# meArm.net
KiCad netlist of a schematic drawn in EAGLE
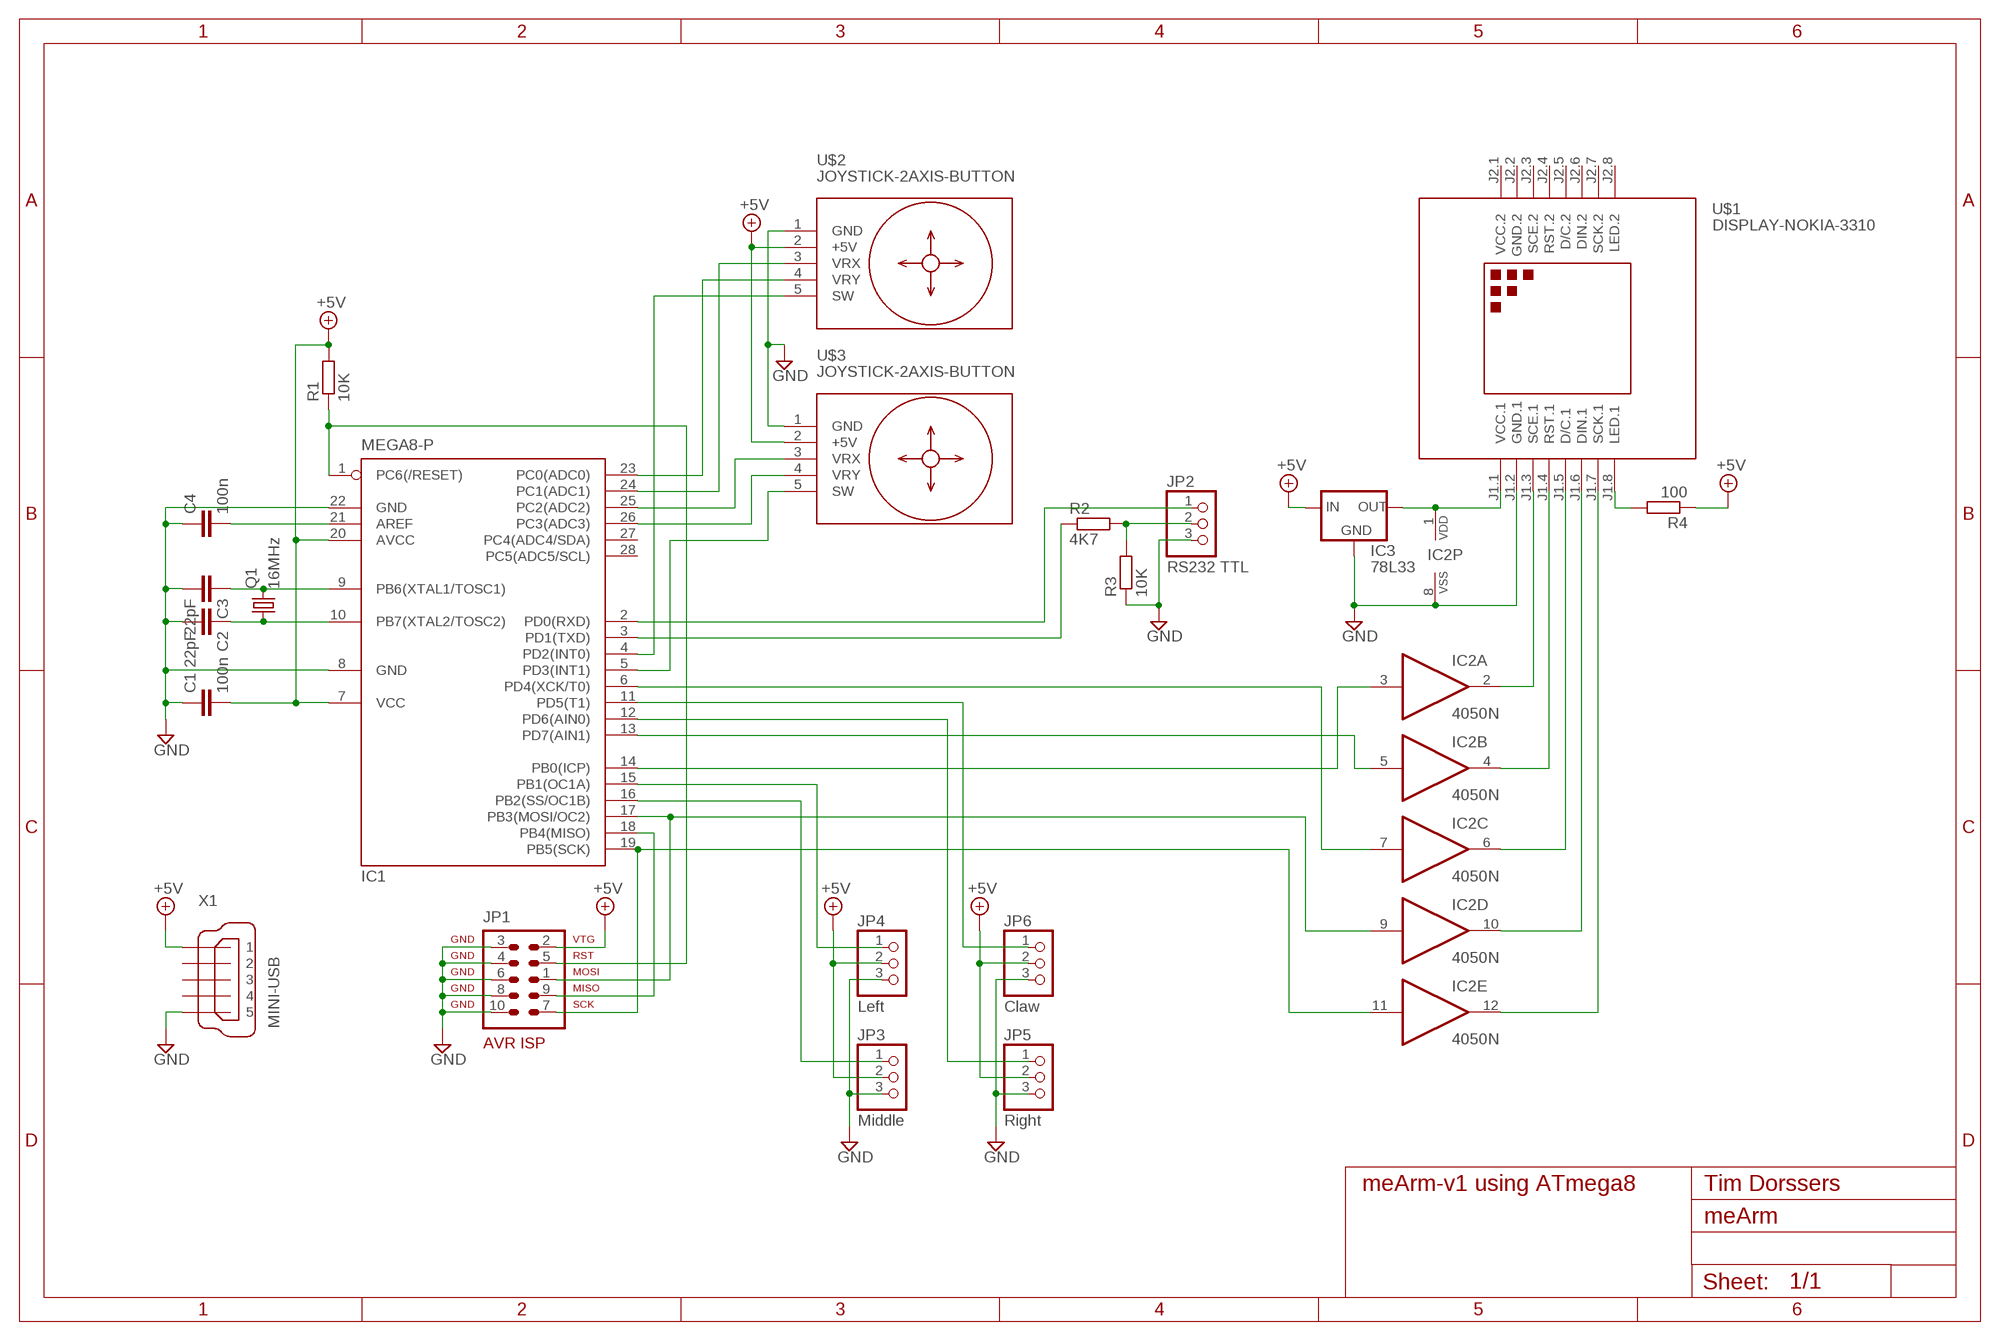
[diagram p0: schematic, sheet 1]

(export (version "E")
  (design (tool "Eeschema 10.0.6"))
  (components
    (comp (ref "C1")
      (value "100n")
      (footprint "eagle-import:C025-025X050")
      (libsource (lib "eagle-import") (part "C-EU025-025X050"))
    )
    (comp (ref "C2")
      (value "22pF")
      (footprint "eagle-import:C025-024X044")
      (libsource (lib "eagle-import") (part "C-EU025-024X044"))
    )
    (comp (ref "C3")
      (value "22pF")
      (footprint "eagle-import:C025-024X044")
      (libsource (lib "eagle-import") (part "C-EU025-024X044"))
    )
    (comp (ref "C4")
      (value "100n")
      (footprint "eagle-import:C025-025X050")
      (libsource (lib "eagle-import") (part "C-EU025-025X050"))
    )
    (comp (ref "IC1")
      (value "MEGA8-P")
      (footprint "eagle-import:DIL28-3")
      (libsource (lib "eagle-import") (part "MEGA8-P"))
    )
    (comp (ref "IC2")
      (value "4050N")
      (footprint "eagle-import:DIL16")
      (libsource (lib "eagle-import") (part "4050N"))
    )
    (comp (ref "IC3")
      (value "78L33")
      (footprint "eagle-import:78LXX")
      (libsource (lib "eagle-import") (part "78LXX"))
    )
    (comp (ref "JP1")
      (value "AVR-ISP-10")
      (footprint "eagle-import:AVR-ISP-10")
      (libsource (lib "eagle-import") (part "AVR-ISP-10"))
    )
    (comp (ref "JP2")
      (value "RS232 TTL")
      (footprint "eagle-import:1X03")
      (libsource (lib "eagle-import") (part "PINHD-1X3"))
    )
    (comp (ref "JP3")
      (value "Middle")
      (footprint "eagle-import:1X03")
      (libsource (lib "eagle-import") (part "PINHD-1X3"))
    )
    (comp (ref "JP4")
      (value "Left")
      (footprint "eagle-import:1X03")
      (libsource (lib "eagle-import") (part "PINHD-1X3"))
    )
    (comp (ref "JP5")
      (value "Right")
      (footprint "eagle-import:1X03")
      (libsource (lib "eagle-import") (part "PINHD-1X3"))
    )
    (comp (ref "JP6")
      (value "Claw")
      (footprint "eagle-import:1X03")
      (libsource (lib "eagle-import") (part "PINHD-1X3"))
    )
    (comp (ref "Q1")
      (value "16MHz")
      (footprint "eagle-import:HC49U-V")
      (libsource (lib "eagle-import") (part "CRYSTALHC49U-V"))
    )
    (comp (ref "R1")
      (value "10K")
      (footprint "eagle-import:0204_7")
      (libsource (lib "eagle-import") (part "resistor_R-EU_0204/7"))
    )
    (comp (ref "R2")
      (value "4K7")
      (footprint "eagle-import:0204_7")
      (libsource (lib "eagle-import") (part "R-EU_0204/7"))
    )
    (comp (ref "R3")
      (value "10K")
      (footprint "eagle-import:0204_7")
      (libsource (lib "eagle-import") (part "R-EU_0204/7"))
    )
    (comp (ref "R4")
      (value "100")
      (footprint "eagle-import:0204_7")
      (libsource (lib "eagle-import") (part "R-EU_0204/7"))
    )
    (comp (ref "U$1")
      (value "DISPLAY-NOKIA-3310")
      (footprint "eagle-import:DISPLAY-NOKIA-3310")
      (libsource (lib "eagle-import") (part "DISPLAY-NOKIA-3310"))
    )
    (comp (ref "U$2")
      (value "JOYSTICK-2AXIS-BUTTON")
      (footprint "eagle-import:JOYSTICK-2AXIS-BUTTON")
      (libsource (lib "eagle-import") (part "JOYSTICK-2AXIS-BUTTON"))
    )
    (comp (ref "U$3")
      (value "JOYSTICK-2AXIS-BUTTON")
      (footprint "eagle-import:JOYSTICK-2AXIS-BUTTON")
      (libsource (lib "eagle-import") (part "JOYSTICK-2AXIS-BUTTON"))
    )
    (comp (ref "X1")
      (value "MINI-USB")
      (footprint "eagle-import:32005-601")
      (libsource (lib "eagle-import") (part "MINI-USB_SHIELD5P2-32005-601"))
    )
  )
  (nets
    (net (code "1") (name "+5V") (class "Default")
      (node (ref "C1") (pin "2") (pinfunction "2_2") (pintype "passive"))
      (node (ref "IC1") (pin "20") (pinfunction "AVCC_20") (pintype "power_in"))
      (node (ref "IC1") (pin "7") (pinfunction "VCC_7") (pintype "power_in"))
      (node (ref "IC3") (pin "IN") (pinfunction "IN_IN") (pintype "input"))
      (node (ref "JP1") (pin "2") (pinfunction "2_2") (pintype "passive"))
      (node (ref "JP3") (pin "2") (pinfunction "2_2") (pintype "passive"))
      (node (ref "JP4") (pin "2") (pinfunction "2_2") (pintype "passive"))
      (node (ref "JP5") (pin "2") (pinfunction "2_2") (pintype "passive"))
      (node (ref "JP6") (pin "2") (pinfunction "2_2") (pintype "passive"))
      (node (ref "R1") (pin "2") (pinfunction "2_2") (pintype "passive"))
      (node (ref "R4") (pin "1") (pinfunction "1_1") (pintype "passive"))
      (node (ref "U$2") (pin "2") (pinfunction "+5V_2") (pintype "power_in"))
      (node (ref "U$3") (pin "2") (pinfunction "+5V_2") (pintype "power_in"))
      (node (ref "X1") (pin "1") (pinfunction "1_1") (pintype "passive"))
    )
    (net (code "2") (name "/GND.2") (class "Default")
      (node (ref "U$1") (pin "J2.2") (pinfunction "GND.2_J2.2") (pintype "power_in"))
    )
    (net (code "3") (name "/VCC.2") (class "Default")
      (node (ref "U$1") (pin "J2.1") (pinfunction "VCC.2_J2.1") (pintype "power_in"))
    )
    (net (code "4") (name "GND") (class "Default")
      (node (ref "C1") (pin "1") (pinfunction "1_1") (pintype "passive"))
      (node (ref "C2") (pin "2") (pinfunction "2_2") (pintype "passive"))
      (node (ref "C3") (pin "2") (pinfunction "2_2") (pintype "passive"))
      (node (ref "C4") (pin "1") (pinfunction "1_1") (pintype "passive"))
      (node (ref "IC1") (pin "22") (pinfunction "GND_22") (pintype "power_in"))
      (node (ref "IC1") (pin "8") (pinfunction "GND_8") (pintype "power_in"))
      (node (ref "IC2") (pin "8") (pinfunction "VSS_8") (pintype "power_in"))
      (node (ref "IC3") (pin "GND") (pinfunction "GND_GND") (pintype "input"))
      (node (ref "JP1") (pin "10") (pinfunction "10_10") (pintype "passive"))
      (node (ref "JP1") (pin "3") (pinfunction "3_3") (pintype "passive"))
      (node (ref "JP1") (pin "4") (pinfunction "4_4") (pintype "passive"))
      (node (ref "JP1") (pin "6") (pinfunction "6_6") (pintype "passive"))
      (node (ref "JP1") (pin "8") (pinfunction "8_8") (pintype "passive"))
      (node (ref "JP2") (pin "3") (pinfunction "3_3") (pintype "passive"))
      (node (ref "JP3") (pin "3") (pinfunction "3_3") (pintype "passive"))
      (node (ref "JP4") (pin "3") (pinfunction "3_3") (pintype "passive"))
      (node (ref "JP5") (pin "3") (pinfunction "3_3") (pintype "passive"))
      (node (ref "JP6") (pin "3") (pinfunction "3_3") (pintype "passive"))
      (node (ref "R3") (pin "1") (pinfunction "1_1") (pintype "passive"))
      (node (ref "U$1") (pin "J1.2") (pinfunction "GND.1_J1.2") (pintype "power_in"))
      (node (ref "U$2") (pin "1") (pinfunction "GND_1") (pintype "power_in"))
      (node (ref "U$3") (pin "1") (pinfunction "GND_1") (pintype "power_in"))
      (node (ref "X1") (pin "5") (pinfunction "5_5") (pintype "passive"))
    )
    (net (code "5") (name "Net-(IC1-AREF)") (class "Default")
      (node (ref "C4") (pin "2") (pinfunction "2_2") (pintype "passive"))
      (node (ref "IC1") (pin "21") (pinfunction "AREF_21") (pintype "passive"))
    )
    (net (code "6") (name "Net-(IC1-PB0(ICP))") (class "Default")
      (node (ref "IC1") (pin "14") (pinfunction "PB0(ICP)_14") (pintype "bidirectional"))
      (node (ref "IC2") (pin "3") (pinfunction "I_3") (pintype "input"))
    )
    (net (code "7") (name "Net-(IC1-PB1(OC1A))") (class "Default")
      (node (ref "IC1") (pin "15") (pinfunction "PB1(OC1A)_15") (pintype "bidirectional"))
      (node (ref "JP4") (pin "1") (pinfunction "1_1") (pintype "passive"))
    )
    (net (code "8") (name "Net-(IC1-PB2(SS{slash}OC1B))") (class "Default")
      (node (ref "IC1") (pin "16") (pinfunction "PB2(SS/OC1B)_16") (pintype "bidirectional"))
      (node (ref "JP3") (pin "1") (pinfunction "1_1") (pintype "passive"))
    )
    (net (code "9") (name "Net-(IC1-PB3(MOSI{slash}OC2))") (class "Default")
      (node (ref "IC1") (pin "17") (pinfunction "PB3(MOSI/OC2)_17") (pintype "bidirectional"))
      (node (ref "IC2") (pin "9") (pinfunction "I_9") (pintype "input"))
      (node (ref "JP1") (pin "1") (pinfunction "1_1") (pintype "passive"))
    )
    (net (code "10") (name "Net-(IC1-PB4(MISO))") (class "Default")
      (node (ref "IC1") (pin "18") (pinfunction "PB4(MISO)_18") (pintype "bidirectional"))
      (node (ref "JP1") (pin "9") (pinfunction "9_9") (pintype "passive"))
    )
    (net (code "11") (name "Net-(IC1-PB5(SCK))") (class "Default")
      (node (ref "IC1") (pin "19") (pinfunction "PB5(SCK)_19") (pintype "bidirectional"))
      (node (ref "IC2") (pin "11") (pinfunction "I_11") (pintype "input"))
      (node (ref "JP1") (pin "7") (pinfunction "7_7") (pintype "passive"))
    )
    (net (code "12") (name "Net-(IC1-PB6(XTAL1{slash}TOSC1))") (class "Default")
      (node (ref "C3") (pin "1") (pinfunction "1_1") (pintype "passive"))
      (node (ref "IC1") (pin "9") (pinfunction "PB6(XTAL1/TOSC1)_9") (pintype "bidirectional"))
      (node (ref "Q1") (pin "2") (pinfunction "2_2") (pintype "passive"))
    )
    (net (code "13") (name "Net-(IC1-PB7(XTAL2{slash}TOSC2))") (class "Default")
      (node (ref "C2") (pin "1") (pinfunction "1_1") (pintype "passive"))
      (node (ref "IC1") (pin "10") (pinfunction "PB7(XTAL2/TOSC2)_10") (pintype "bidirectional"))
      (node (ref "Q1") (pin "1") (pinfunction "1_1") (pintype "passive"))
    )
    (net (code "14") (name "Net-(IC1-PC0(ADC0))") (class "Default")
      (node (ref "IC1") (pin "23") (pinfunction "PC0(ADC0)_23") (pintype "bidirectional"))
      (node (ref "U$2") (pin "4") (pinfunction "VRY_4") (pintype "passive"))
    )
    (net (code "15") (name "Net-(IC1-PC1(ADC1))") (class "Default")
      (node (ref "IC1") (pin "24") (pinfunction "PC1(ADC1)_24") (pintype "bidirectional"))
      (node (ref "U$2") (pin "3") (pinfunction "VRX_3") (pintype "passive"))
    )
    (net (code "16") (name "Net-(IC1-PC2(ADC2))") (class "Default")
      (node (ref "IC1") (pin "25") (pinfunction "PC2(ADC2)_25") (pintype "bidirectional"))
      (node (ref "U$3") (pin "3") (pinfunction "VRX_3") (pintype "passive"))
    )
    (net (code "17") (name "Net-(IC1-PC3(ADC3))") (class "Default")
      (node (ref "IC1") (pin "26") (pinfunction "PC3(ADC3)_26") (pintype "bidirectional"))
      (node (ref "U$3") (pin "4") (pinfunction "VRY_4") (pintype "passive"))
    )
    (net (code "18") (name "Net-(IC1-PC6({slash}RESET))") (class "Default")
      (node (ref "IC1") (pin "1") (pinfunction "PC6(/RESET)_1") (pintype "bidirectional"))
      (node (ref "JP1") (pin "5") (pinfunction "5_5") (pintype "passive"))
      (node (ref "R1") (pin "1") (pinfunction "1_1") (pintype "passive"))
    )
    (net (code "19") (name "Net-(IC1-PD0(RXD))") (class "Default")
      (node (ref "IC1") (pin "2") (pinfunction "PD0(RXD)_2") (pintype "bidirectional"))
      (node (ref "JP2") (pin "1") (pinfunction "1_1") (pintype "passive"))
    )
    (net (code "20") (name "Net-(IC1-PD1(TXD))") (class "Default")
      (node (ref "IC1") (pin "3") (pinfunction "PD1(TXD)_3") (pintype "bidirectional"))
      (node (ref "R2") (pin "1") (pinfunction "1_1") (pintype "passive"))
    )
    (net (code "21") (name "Net-(IC1-PD2(INT0))") (class "Default")
      (node (ref "IC1") (pin "4") (pinfunction "PD2(INT0)_4") (pintype "bidirectional"))
      (node (ref "U$2") (pin "5") (pinfunction "SW_5") (pintype "passive"))
    )
    (net (code "22") (name "Net-(IC1-PD3(INT1))") (class "Default")
      (node (ref "IC1") (pin "5") (pinfunction "PD3(INT1)_5") (pintype "bidirectional"))
      (node (ref "U$3") (pin "5") (pinfunction "SW_5") (pintype "passive"))
    )
    (net (code "23") (name "Net-(IC1-PD4(XCK{slash}T0))") (class "Default")
      (node (ref "IC1") (pin "6") (pinfunction "PD4(XCK/T0)_6") (pintype "bidirectional"))
      (node (ref "IC2") (pin "7") (pinfunction "I_7") (pintype "input"))
    )
    (net (code "24") (name "Net-(IC1-PD5(T1))") (class "Default")
      (node (ref "IC1") (pin "11") (pinfunction "PD5(T1)_11") (pintype "bidirectional"))
      (node (ref "JP6") (pin "1") (pinfunction "1_1") (pintype "passive"))
    )
    (net (code "25") (name "Net-(IC1-PD6(AIN0))") (class "Default")
      (node (ref "IC1") (pin "12") (pinfunction "PD6(AIN0)_12") (pintype "bidirectional"))
      (node (ref "JP5") (pin "1") (pinfunction "1_1") (pintype "passive"))
    )
    (net (code "26") (name "Net-(IC1-PD7(AIN1))") (class "Default")
      (node (ref "IC1") (pin "13") (pinfunction "PD7(AIN1)_13") (pintype "bidirectional"))
      (node (ref "IC2") (pin "5") (pinfunction "I_5") (pintype "input"))
    )
    (net (code "27") (name "Net-(IC2A-O)") (class "Default")
      (node (ref "IC2") (pin "2") (pinfunction "O_2") (pintype "output"))
      (node (ref "U$1") (pin "J1.3") (pinfunction "SCE.1_J1.3") (pintype "bidirectional"))
    )
    (net (code "28") (name "Net-(IC2B-O)") (class "Default")
      (node (ref "IC2") (pin "4") (pinfunction "O_4") (pintype "output"))
      (node (ref "U$1") (pin "J1.4") (pinfunction "RST.1_J1.4") (pintype "bidirectional"))
    )
    (net (code "29") (name "Net-(IC2C-O)") (class "Default")
      (node (ref "IC2") (pin "6") (pinfunction "O_6") (pintype "output"))
      (node (ref "U$1") (pin "J1.5") (pinfunction "D/C.1_J1.5") (pintype "bidirectional"))
    )
    (net (code "30") (name "Net-(IC2D-O)") (class "Default")
      (node (ref "IC2") (pin "10") (pinfunction "O_10") (pintype "output"))
      (node (ref "U$1") (pin "J1.6") (pinfunction "DIN.1_J1.6") (pintype "bidirectional"))
    )
    (net (code "31") (name "Net-(IC2E-O)") (class "Default")
      (node (ref "IC2") (pin "12") (pinfunction "O_12") (pintype "output"))
      (node (ref "U$1") (pin "J1.7") (pinfunction "SCK.1_J1.7") (pintype "bidirectional"))
    )
    (net (code "32") (name "Net-(IC2G-VDD)") (class "Default")
      (node (ref "IC2") (pin "1") (pinfunction "VDD_1") (pintype "power_in"))
      (node (ref "IC3") (pin "OUT") (pinfunction "OUT_OUT") (pintype "passive"))
      (node (ref "U$1") (pin "J1.1") (pinfunction "VCC.1_J1.1") (pintype "power_in"))
    )
    (net (code "33") (name "Net-(JP2-Pad2)") (class "Default")
      (node (ref "JP2") (pin "2") (pinfunction "2_2") (pintype "passive"))
      (node (ref "R2") (pin "2") (pinfunction "2_2") (pintype "passive"))
      (node (ref "R3") (pin "2") (pinfunction "2_2") (pintype "passive"))
    )
    (net (code "34") (name "Net-(U$1-LED.1)") (class "Default")
      (node (ref "R4") (pin "2") (pinfunction "2_2") (pintype "passive"))
      (node (ref "U$1") (pin "J1.8") (pinfunction "LED.1_J1.8") (pintype "input"))
    )
    (net (code "35") (name "unconnected-(IC1-PC4(ADC4{slash}SDA)-Pad27)") (class "Default")
      (node (ref "IC1") (pin "27") (pinfunction "PC4(ADC4/SDA)_27") (pintype "bidirectional"))
    )
    (net (code "36") (name "unconnected-(IC1-PC5(ADC5{slash}SCL)-Pad28)") (class "Default")
      (node (ref "IC1") (pin "28") (pinfunction "PC5(ADC5/SCL)_28") (pintype "bidirectional"))
    )
    (net (code "37") (name "unconnected-(U$1-DIN.2-PadJ2.6)") (class "Default")
      (node (ref "U$1") (pin "J2.6") (pinfunction "DIN.2_J2.6") (pintype "bidirectional"))
    )
    (net (code "38") (name "unconnected-(U$1-D{slash}C.2-PadJ2.5)") (class "Default")
      (node (ref "U$1") (pin "J2.5") (pinfunction "D/C.2_J2.5") (pintype "bidirectional"))
    )
    (net (code "39") (name "unconnected-(U$1-LED.2-PadJ2.8)") (class "Default")
      (node (ref "U$1") (pin "J2.8") (pinfunction "LED.2_J2.8") (pintype "input"))
    )
    (net (code "40") (name "unconnected-(U$1-RST.2-PadJ2.4)") (class "Default")
      (node (ref "U$1") (pin "J2.4") (pinfunction "RST.2_J2.4") (pintype "bidirectional"))
    )
    (net (code "41") (name "unconnected-(U$1-SCE.2-PadJ2.3)") (class "Default")
      (node (ref "U$1") (pin "J2.3") (pinfunction "SCE.2_J2.3") (pintype "bidirectional"))
    )
    (net (code "42") (name "unconnected-(U$1-SCK.2-PadJ2.7)") (class "Default")
      (node (ref "U$1") (pin "J2.7") (pinfunction "SCK.2_J2.7") (pintype "bidirectional"))
    )
    (net (code "43") (name "unconnected-(X1-Pad2)") (class "Default")
      (node (ref "X1") (pin "2") (pinfunction "2_2") (pintype "passive"))
    )
    (net (code "44") (name "unconnected-(X1-Pad3)") (class "Default")
      (node (ref "X1") (pin "3") (pinfunction "3_3") (pintype "passive"))
    )
    (net (code "45") (name "unconnected-(X1-Pad4)") (class "Default")
      (node (ref "X1") (pin "4") (pinfunction "4_4") (pintype "passive"))
    )
  )
)
